# 7419_SUPPLY.net
KiCad netlist of a schematic drawn in Altium Designer
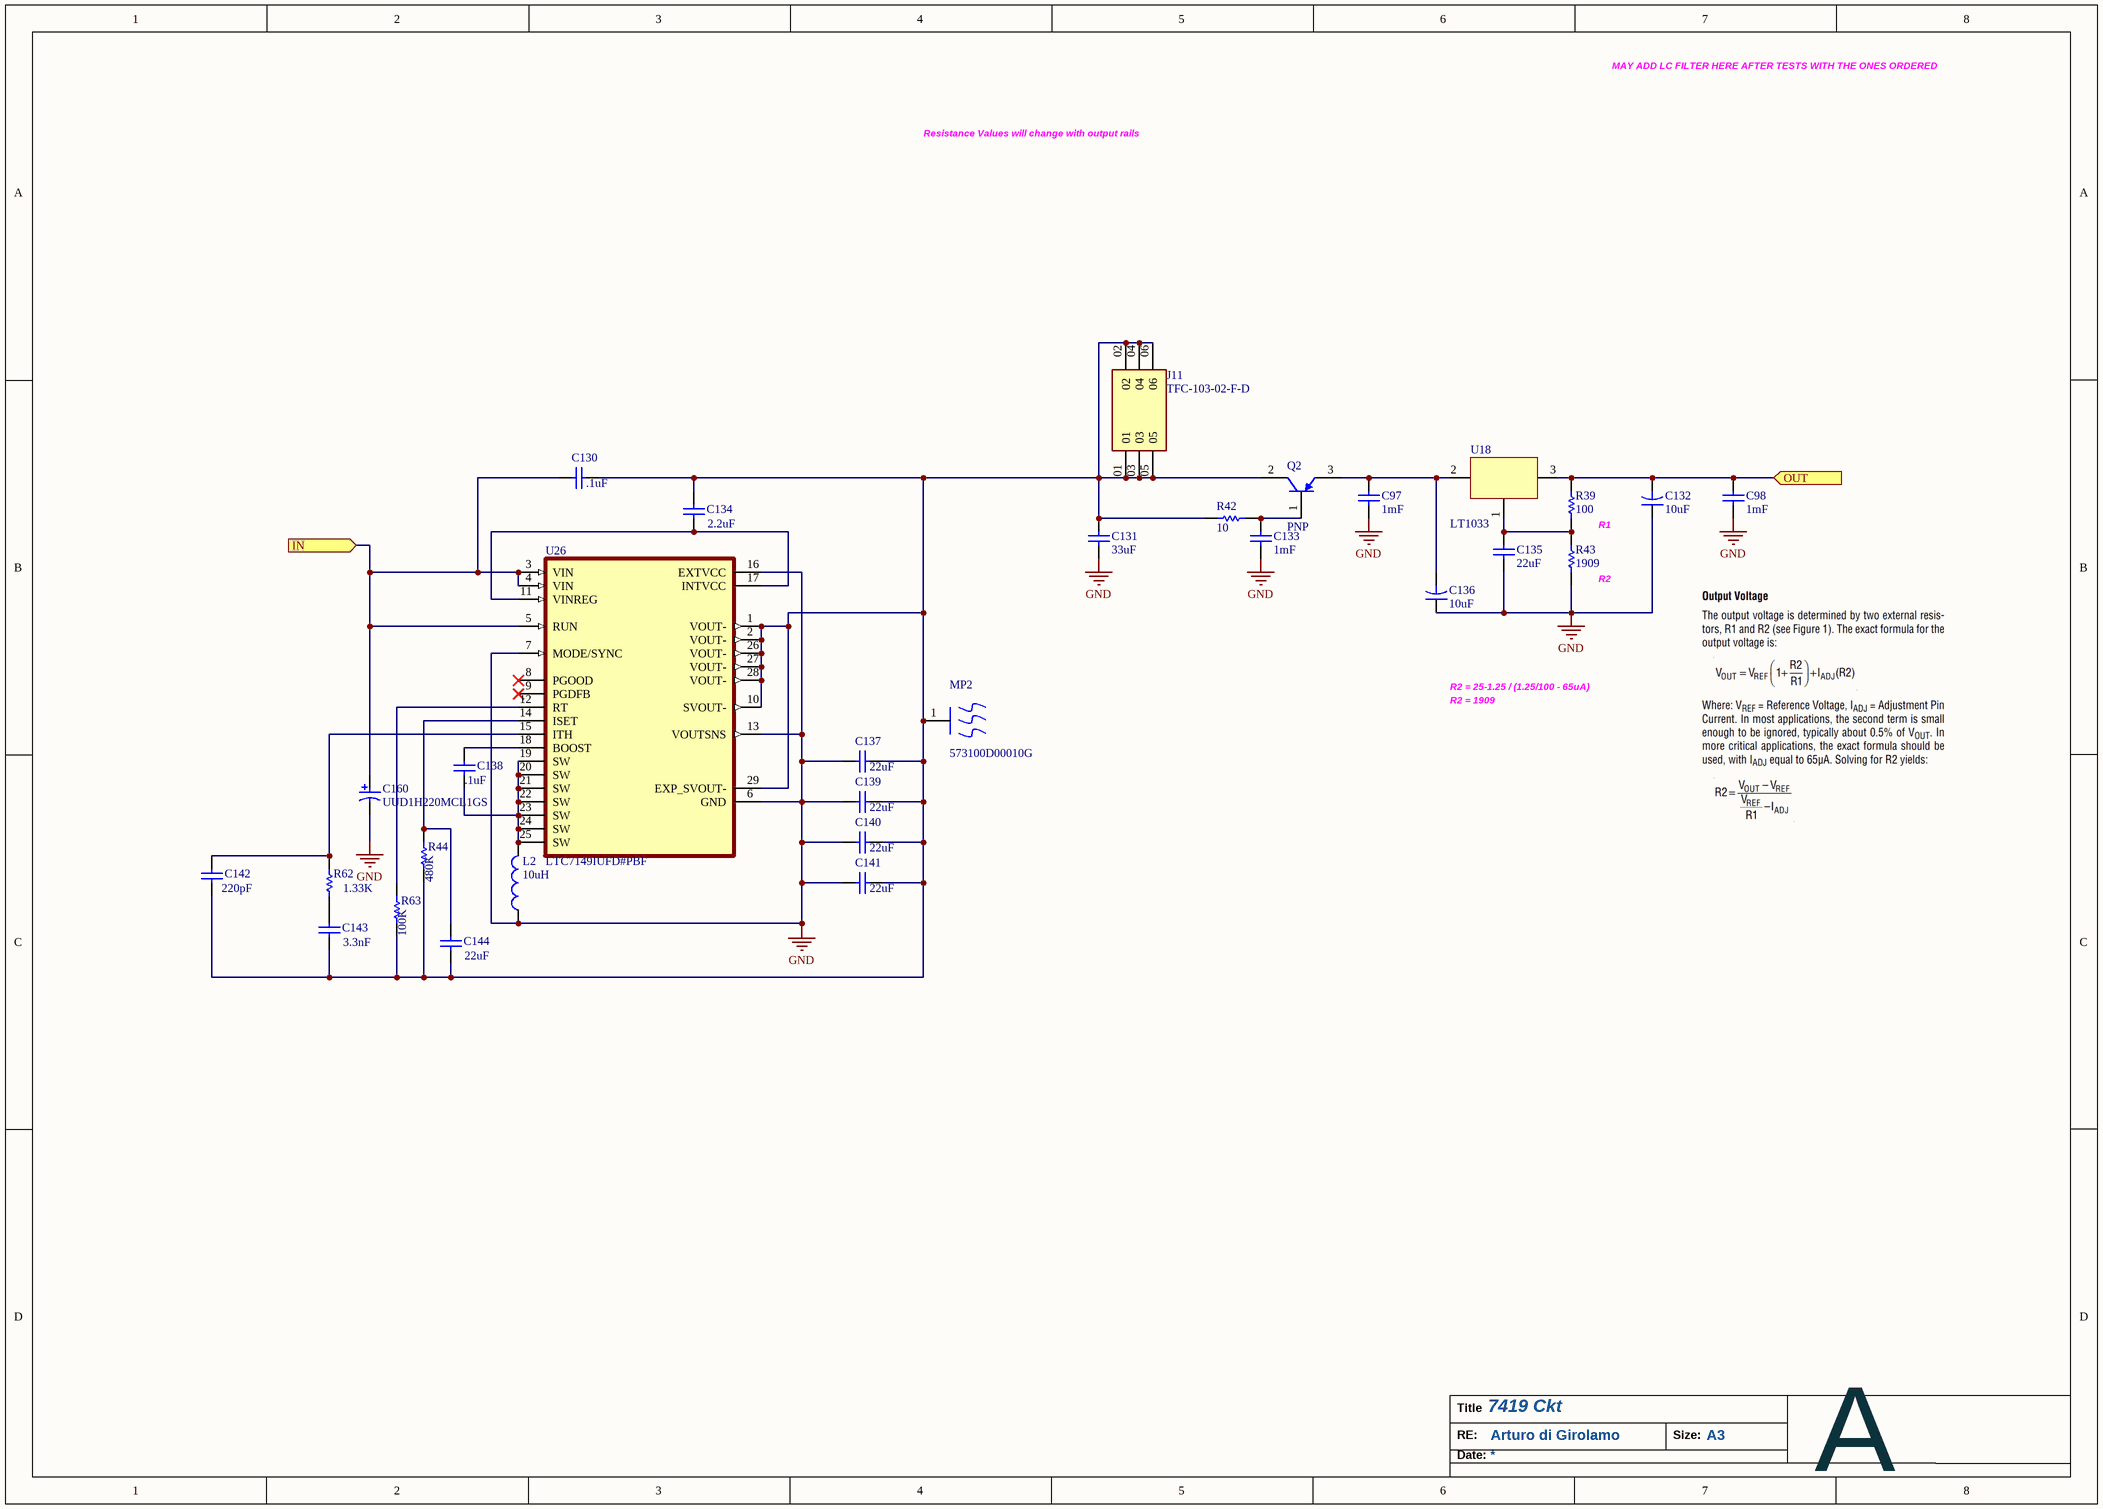
[diagram p0: 7419_SUPPLY.SchDoc]

(export (version "E")
  (design (tool "Eeschema 10.0.6"))
  (components
    (comp (ref "C97")
      (value "1mF")
      (footprint "EEVFK1V152M")
      (description "Capacitor, 1mF 50V")
      (libsource (lib "Arturo_Approved") (part "EEV-FK1H102M"))
    )
    (comp (ref "C98")
      (value "1mF")
      (footprint "EEVFK1V152M")
      (description "Capacitor, 1mF 50V")
      (libsource (lib "Arturo_Approved") (part "EEV-FK1H102M"))
    )
    (comp (ref "C130")
      (value ".1uF")
      (footprint "6-0805_M")
      (description "Capacitor")
      (fields (field (name "Comment") "478-10836-1-ND") (field (name "PUBLISHER") "Altium Limited"))
      (libsource (lib "Miscellaneous Devices") (part "Cap"))
    )
    (comp (ref "C131")
      (value "33uF")
      (footprint "6-0805_M")
      (description "Capacitor")
      (fields (field (name "Comment") "490-10749-1-ND") (field (name "PUBLISHER") "Altium Limited"))
      (libsource (lib "Miscellaneous Devices") (part "Cap"))
    )
    (comp (ref "C132")
      (value "10uF")
      (footprint "Tantalum_2917")
      (description "Capacitor, 100uF NICHICON")
      (libsource (lib "Arturo_Approved") (part "UVR1V102MHD1TO"))
    )
    (comp (ref "C133")
      (value "1mF")
      (footprint "EEVFK1V152M")
      (description "Capacitor, 1mF 50V")
      (libsource (lib "Arturo_Approved") (part "EEV-FK1H102M"))
    )
    (comp (ref "C134")
      (value "2.2uF")
      (footprint "6-0805_M")
      (description "Capacitor")
      (fields (field (name "Comment") "1276-6458-1-ND") (field (name "PUBLISHER") "Altium Limited"))
      (libsource (lib "Miscellaneous Devices") (part "Cap"))
    )
    (comp (ref "C135")
      (value "22uF")
      (footprint "6-0805_M")
      (description "Capacitor")
      (fields (field (name "Comment") "490-10749-1-ND") (field (name "PUBLISHER") "Altium Limited"))
      (libsource (lib "Miscellaneous Devices") (part "Cap"))
    )
    (comp (ref "C136")
      (value "10uF")
      (footprint "Tantalum_2917")
      (description "Capacitor, 100uF NICHICON")
      (libsource (lib "Arturo_Approved") (part "UVR1V102MHD1TO"))
    )
    (comp (ref "C137")
      (value "22uF")
      (footprint "6-0805_M")
      (description "Capacitor")
      (fields (field (name "Comment") "490-10749-1-ND") (field (name "PUBLISHER") "Altium Limited"))
      (libsource (lib "Miscellaneous Devices") (part "Cap"))
    )
    (comp (ref "C138")
      (value ".1uF")
      (footprint "6-0805_M")
      (description "Capacitor")
      (fields (field (name "Comment") "478-10836-1-ND") (field (name "PUBLISHER") "Altium Limited"))
      (libsource (lib "Miscellaneous Devices") (part "Cap"))
    )
    (comp (ref "C139")
      (value "22uF")
      (footprint "6-0805_M")
      (description "Capacitor")
      (fields (field (name "Comment") "490-10749-1-ND") (field (name "PUBLISHER") "Altium Limited"))
      (libsource (lib "Miscellaneous Devices") (part "Cap"))
    )
    (comp (ref "C140")
      (value "22uF")
      (footprint "6-0805_M")
      (description "Capacitor")
      (fields (field (name "Comment") "490-10749-1-ND") (field (name "PUBLISHER") "Altium Limited"))
      (libsource (lib "Miscellaneous Devices") (part "Cap"))
    )
    (comp (ref "C141")
      (value "22uF")
      (footprint "6-0805_M")
      (description "Capacitor")
      (fields (field (name "Comment") "490-10749-1-ND") (field (name "PUBLISHER") "Altium Limited"))
      (libsource (lib "Miscellaneous Devices") (part "Cap"))
    )
    (comp (ref "C142")
      (value "220pF")
      (footprint "6-0805_M")
      (description "Capacitor")
      (fields (field (name "Comment") "399-1151-1-ND") (field (name "PUBLISHER") "Altium Limited"))
      (libsource (lib "Miscellaneous Devices") (part "Cap"))
    )
    (comp (ref "C143")
      (value "3.3nF")
      (footprint "6-0805_M")
      (description "Capacitor")
      (fields (field (name "Comment") "399-1153-1-ND") (field (name "PUBLISHER") "Altium Limited"))
      (libsource (lib "Miscellaneous Devices") (part "Cap"))
    )
    (comp (ref "C144")
      (value "22uF")
      (footprint "6-0805_M")
      (description "Capacitor")
      (fields (field (name "Comment") "399-7994-1-ND") (field (name "PUBLISHER") "Altium Limited"))
      (libsource (lib "Miscellaneous Devices") (part "Cap"))
    )
    (comp (ref "C160")
      (value "UUD1H220MCL1GS")
      (footprint "NIC-CAPA2-6.3X5.8_V")
      (fields (field (name "MANUFACTURER") "Nichicon"))
      (libsource (lib "Altium Content Vault") (part "NIC-CAP-P-2"))
    )
    (comp (ref "J11")
      (value "TFC-103-02-F-D")
      (footprint "Arturo_Approved:SAMTEC_TFC-103-02-F-D")
      (fields (field (name "MF") "Samtec"))
      (libsource (lib "Arturo_Approved") (part "TFC-103-02-F-D"))
    )
    (comp (ref "L2")
      (value "10uH")
      (footprint "IHLP2020BZER100M01")
      (description "Inductor 10uH VISHAY")
      (libsource (lib "Arturo_Approved") (part "IHLP2020BZER100M01"))
    )
    (comp (ref "MP2")
      (value "573100D00010G")
      (footprint "FP-573100D00010G-MFG")
      (description "HEATSINK SMT D-PAK/TO-252 TIN")
      (fields
        (field (name "OCTOPART") "https://octopart.com/573100d00010g-aavid+thermalloy-807578")
        (field (name "MANUFACTURER") "Aavid Thermalloy")
      )
      (libsource (lib "Altium Content Vault") (part "142a89880038802df2e3ee021ca9915"))
    )
    (comp (ref "Q2")
      (value "PNP")
      (footprint "TO-220-3")
      (description "PNP General Purpose Amplifier")
      (fields (field (name "PUBLISHER") "Altium Limited"))
      (libsource (lib "Arturo_Approved") (part "PNP"))
    )
    (comp (ref "R39")
      (value "100")
      (footprint "2512_SMD")
      (description "100K 1% 1/10W")
      (libsource (lib "Arturo_Approved") (part "RR1220P-104-D"))
    )
    (comp (ref "R42")
      (value "10")
      (footprint "2512_SMD")
      (description "10 ohm 0805")
      (libsource (lib "Arturo_Approved") (part "RNCF0805DTE10R0"))
    )
    (comp (ref "R43")
      (value "1909")
      (footprint "2512_SMD")
      (description "100K 1% 1/10W")
      (libsource (lib "Arturo_Approved") (part "RR1220P-104-D"))
    )
    (comp (ref "R44")
      (value "480K")
      (footprint "6-0805_M")
      (description "Resistor")
      (fields (field (name "Comment") "311-360KCRCT-ND") (field (name "PUBLISHER") "Altium Limited"))
      (libsource (lib "Miscellaneous Devices") (part "Res1"))
    )
    (comp (ref "R62")
      (value "1.33K")
      (footprint "6-0805_M")
      (description "Resistor")
      (fields (field (name "Comment") "P20607CT-ND") (field (name "PUBLISHER") "Altium Limited"))
      (libsource (lib "Miscellaneous Devices") (part "Res1"))
    )
    (comp (ref "R63")
      (value "100K")
      (footprint "6-0805_M")
      (description "Resistor")
      (fields (field (name "Comment") "P100KCCT-ND") (field (name "PUBLISHER") "Altium Limited"))
      (libsource (lib "Miscellaneous Devices") (part "Res1"))
    )
    (comp (ref "U18")
      (value "LT1033")
      (footprint "TO-220-3")
      (libsource (lib "Arturo_Approved") (part "LT337"))
    )
    (comp (ref "U26")
      (value "LTC7149IUFD#PBF")
      (footprint "QFN50P500X400X80-29N")
      (libsource (lib "Arturo_Approved") (part "LTC7149IUFD#PBF"))
    )
  )
  (nets
    (net (code "1") (name "/IN") (class "Default")
      (node (ref "C130") (pin "2") (pinfunction "2_2") (pintype "passive"))
      (node (ref "C160") (pin "1") (pinfunction "1_1") (pintype "passive"))
      (node (ref "U26") (pin "3") (pinfunction "VIN_3") (pintype "input"))
      (node (ref "U26") (pin "4") (pinfunction "VIN_4") (pintype "input"))
      (node (ref "U26") (pin "5") (pinfunction "RUN_5") (pintype "input"))
    )
    (net (code "2") (name "/OUT") (class "Default")
      (node (ref "C132") (pin "2") (pinfunction "2_2") (pintype "passive"))
      (node (ref "C98") (pin "2") (pinfunction "2_2") (pintype "passive"))
      (node (ref "R39") (pin "2") (pinfunction "2_2") (pintype "passive"))
      (node (ref "U18") (pin "3") (pinfunction "3_3") (pintype "passive"))
    )
    (net (code "3") (name "GND") (class "Default")
      (node (ref "C131") (pin "2") (pinfunction "2_2") (pintype "passive"))
      (node (ref "C132") (pin "1") (pinfunction "1_1") (pintype "passive"))
      (node (ref "C133") (pin "1") (pinfunction "1_1") (pintype "passive"))
      (node (ref "C135") (pin "2") (pinfunction "2_2") (pintype "passive"))
      (node (ref "C136") (pin "1") (pinfunction "1_1") (pintype "passive"))
      (node (ref "C137") (pin "2") (pinfunction "2_2") (pintype "passive"))
      (node (ref "C139") (pin "2") (pinfunction "2_2") (pintype "passive"))
      (node (ref "C140") (pin "2") (pinfunction "2_2") (pintype "passive"))
      (node (ref "C141") (pin "2") (pinfunction "2_2") (pintype "passive"))
      (node (ref "C160") (pin "2") (pinfunction "2_2") (pintype "passive"))
      (node (ref "C97") (pin "1") (pinfunction "1_1") (pintype "passive"))
      (node (ref "C98") (pin "1") (pinfunction "1_1") (pintype "passive"))
      (node (ref "L2") (pin "1") (pinfunction "1_1") (pintype "passive"))
      (node (ref "R43") (pin "1") (pinfunction "1_1") (pintype "passive"))
      (node (ref "U26") (pin "13") (pinfunction "VOUTSNS_13") (pintype "output"))
      (node (ref "U26") (pin "16") (pinfunction "EXTVCC_16") (pintype "power_in"))
      (node (ref "U26") (pin "6") (pinfunction "GND_6") (pintype "power_in"))
      (node (ref "U26") (pin "7") (pinfunction "MODE/SYNC_7") (pintype "input"))
    )
    (net (code "4") (name "Net-(C135-Pad1)") (class "Default")
      (node (ref "C135") (pin "1") (pinfunction "1_1") (pintype "passive"))
      (node (ref "R39") (pin "1") (pinfunction "1_1") (pintype "passive"))
      (node (ref "R43") (pin "2") (pinfunction "2_2") (pintype "passive"))
      (node (ref "U18") (pin "1") (pinfunction "1_1") (pintype "passive"))
    )
    (net (code "5") (name "Net-(C138-Pad2)") (class "Default")
      (node (ref "C138") (pin "2") (pinfunction "2_2") (pintype "passive"))
      (node (ref "L2") (pin "2") (pinfunction "2_2") (pintype "passive"))
      (node (ref "U26") (pin "19") (pinfunction "SW_19") (pintype "passive"))
      (node (ref "U26") (pin "20") (pinfunction "SW_20") (pintype "passive"))
      (node (ref "U26") (pin "21") (pinfunction "SW_21") (pintype "passive"))
      (node (ref "U26") (pin "22") (pinfunction "SW_22") (pintype "passive"))
      (node (ref "U26") (pin "23") (pinfunction "SW_23") (pintype "passive"))
      (node (ref "U26") (pin "24") (pinfunction "SW_24") (pintype "passive"))
      (node (ref "U26") (pin "25") (pinfunction "SW_25") (pintype "passive"))
    )
    (net (code "6") (name "Net-(C143-Pad1)") (class "Default")
      (node (ref "C143") (pin "1") (pinfunction "1_1") (pintype "passive"))
      (node (ref "R62") (pin "1") (pinfunction "1_1") (pintype "passive"))
    )
    (net (code "7") (name "Net-(Q2-B)") (class "Default")
      (node (ref "C133") (pin "2") (pinfunction "2_2") (pintype "passive"))
      (node (ref "Q2") (pin "1") (pinfunction "B_1") (pintype "passive"))
      (node (ref "R42") (pin "2") (pinfunction "2_2") (pintype "passive"))
    )
    (net (code "8") (name "Net-(Q2-C)") (class "Default")
      (node (ref "C130") (pin "1") (pinfunction "1_1") (pintype "passive"))
      (node (ref "C131") (pin "1") (pinfunction "1_1") (pintype "passive"))
      (node (ref "C134") (pin "2") (pinfunction "2_2") (pintype "passive"))
      (node (ref "C137") (pin "1") (pinfunction "1_1") (pintype "passive"))
      (node (ref "C139") (pin "1") (pinfunction "1_1") (pintype "passive"))
      (node (ref "C140") (pin "1") (pinfunction "1_1") (pintype "passive"))
      (node (ref "C141") (pin "1") (pinfunction "1_1") (pintype "passive"))
      (node (ref "C142") (pin "2") (pinfunction "2_2") (pintype "passive"))
      (node (ref "C143") (pin "2") (pinfunction "2_2") (pintype "passive"))
      (node (ref "C144") (pin "2") (pinfunction "2_2") (pintype "passive"))
      (node (ref "J11") (pin "01") (pinfunction "01_01") (pintype "passive"))
      (node (ref "J11") (pin "02") (pinfunction "02_02") (pintype "passive"))
      (node (ref "J11") (pin "03") (pinfunction "03_03") (pintype "passive"))
      (node (ref "J11") (pin "04") (pinfunction "04_04") (pintype "passive"))
      (node (ref "J11") (pin "05") (pinfunction "05_05") (pintype "passive"))
      (node (ref "J11") (pin "06") (pinfunction "06_06") (pintype "passive"))
      (node (ref "MP2") (pin "1") (pinfunction "1_1") (pintype "passive"))
      (node (ref "Q2") (pin "2") (pinfunction "C_2") (pintype "passive"))
      (node (ref "R42") (pin "1") (pinfunction "1_1") (pintype "passive"))
      (node (ref "R44") (pin "1") (pinfunction "1_1") (pintype "passive"))
      (node (ref "R63") (pin "1") (pinfunction "1_1") (pintype "passive"))
      (node (ref "U26") (pin "1") (pinfunction "VOUT-_1") (pintype "output"))
      (node (ref "U26") (pin "10") (pinfunction "SVOUT-_10") (pintype "output"))
      (node (ref "U26") (pin "2") (pinfunction "VOUT-_2") (pintype "output"))
      (node (ref "U26") (pin "26") (pinfunction "VOUT-_26") (pintype "output"))
      (node (ref "U26") (pin "27") (pinfunction "VOUT-_27") (pintype "output"))
      (node (ref "U26") (pin "28") (pinfunction "VOUT-_28") (pintype "output"))
      (node (ref "U26") (pin "29") (pinfunction "EXP_SVOUT-_29") (pintype "power_in"))
    )
    (net (code "9") (name "Net-(Q2-E)") (class "Default")
      (node (ref "C136") (pin "2") (pinfunction "2_2") (pintype "passive"))
      (node (ref "C97") (pin "2") (pinfunction "2_2") (pintype "passive"))
      (node (ref "Q2") (pin "3") (pinfunction "E_3") (pintype "passive"))
      (node (ref "U18") (pin "2") (pinfunction "2_2") (pintype "passive"))
    )
    (net (code "10") (name "Net-(U26-BOOST)") (class "Default")
      (node (ref "C138") (pin "1") (pinfunction "1_1") (pintype "passive"))
      (node (ref "U26") (pin "18") (pinfunction "BOOST_18") (pintype "passive"))
    )
    (net (code "11") (name "Net-(U26-INTVCC)") (class "Default")
      (node (ref "C134") (pin "1") (pinfunction "1_1") (pintype "passive"))
      (node (ref "U26") (pin "11") (pinfunction "VINREG_11") (pintype "input"))
      (node (ref "U26") (pin "17") (pinfunction "INTVCC_17") (pintype "power_in"))
    )
    (net (code "12") (name "Net-(U26-ISET)") (class "Default")
      (node (ref "C144") (pin "1") (pinfunction "1_1") (pintype "passive"))
      (node (ref "R44") (pin "2") (pinfunction "2_2") (pintype "passive"))
      (node (ref "U26") (pin "14") (pinfunction "ISET_14") (pintype "passive"))
    )
    (net (code "13") (name "Net-(U26-ITH)") (class "Default")
      (node (ref "C142") (pin "1") (pinfunction "1_1") (pintype "passive"))
      (node (ref "R62") (pin "2") (pinfunction "2_2") (pintype "passive"))
      (node (ref "U26") (pin "15") (pinfunction "ITH_15") (pintype "passive"))
    )
    (net (code "14") (name "Net-(U26-RT)") (class "Default")
      (node (ref "R63") (pin "2") (pinfunction "2_2") (pintype "passive"))
      (node (ref "U26") (pin "12") (pinfunction "RT_12") (pintype "passive"))
    )
    (net (code "15") (name "unconnected-(U26-PGDFB-Pad9)") (class "Default")
      (node (ref "U26") (pin "9") (pinfunction "PGDFB_9") (pintype "passive+no_connect"))
    )
    (net (code "16") (name "unconnected-(U26-PGOOD-Pad8)") (class "Default")
      (node (ref "U26") (pin "8") (pinfunction "PGOOD_8") (pintype "passive+no_connect"))
    )
  )
)
